# imu_3_xy.net
KiCad netlist of a schematic drawn in EAGLE
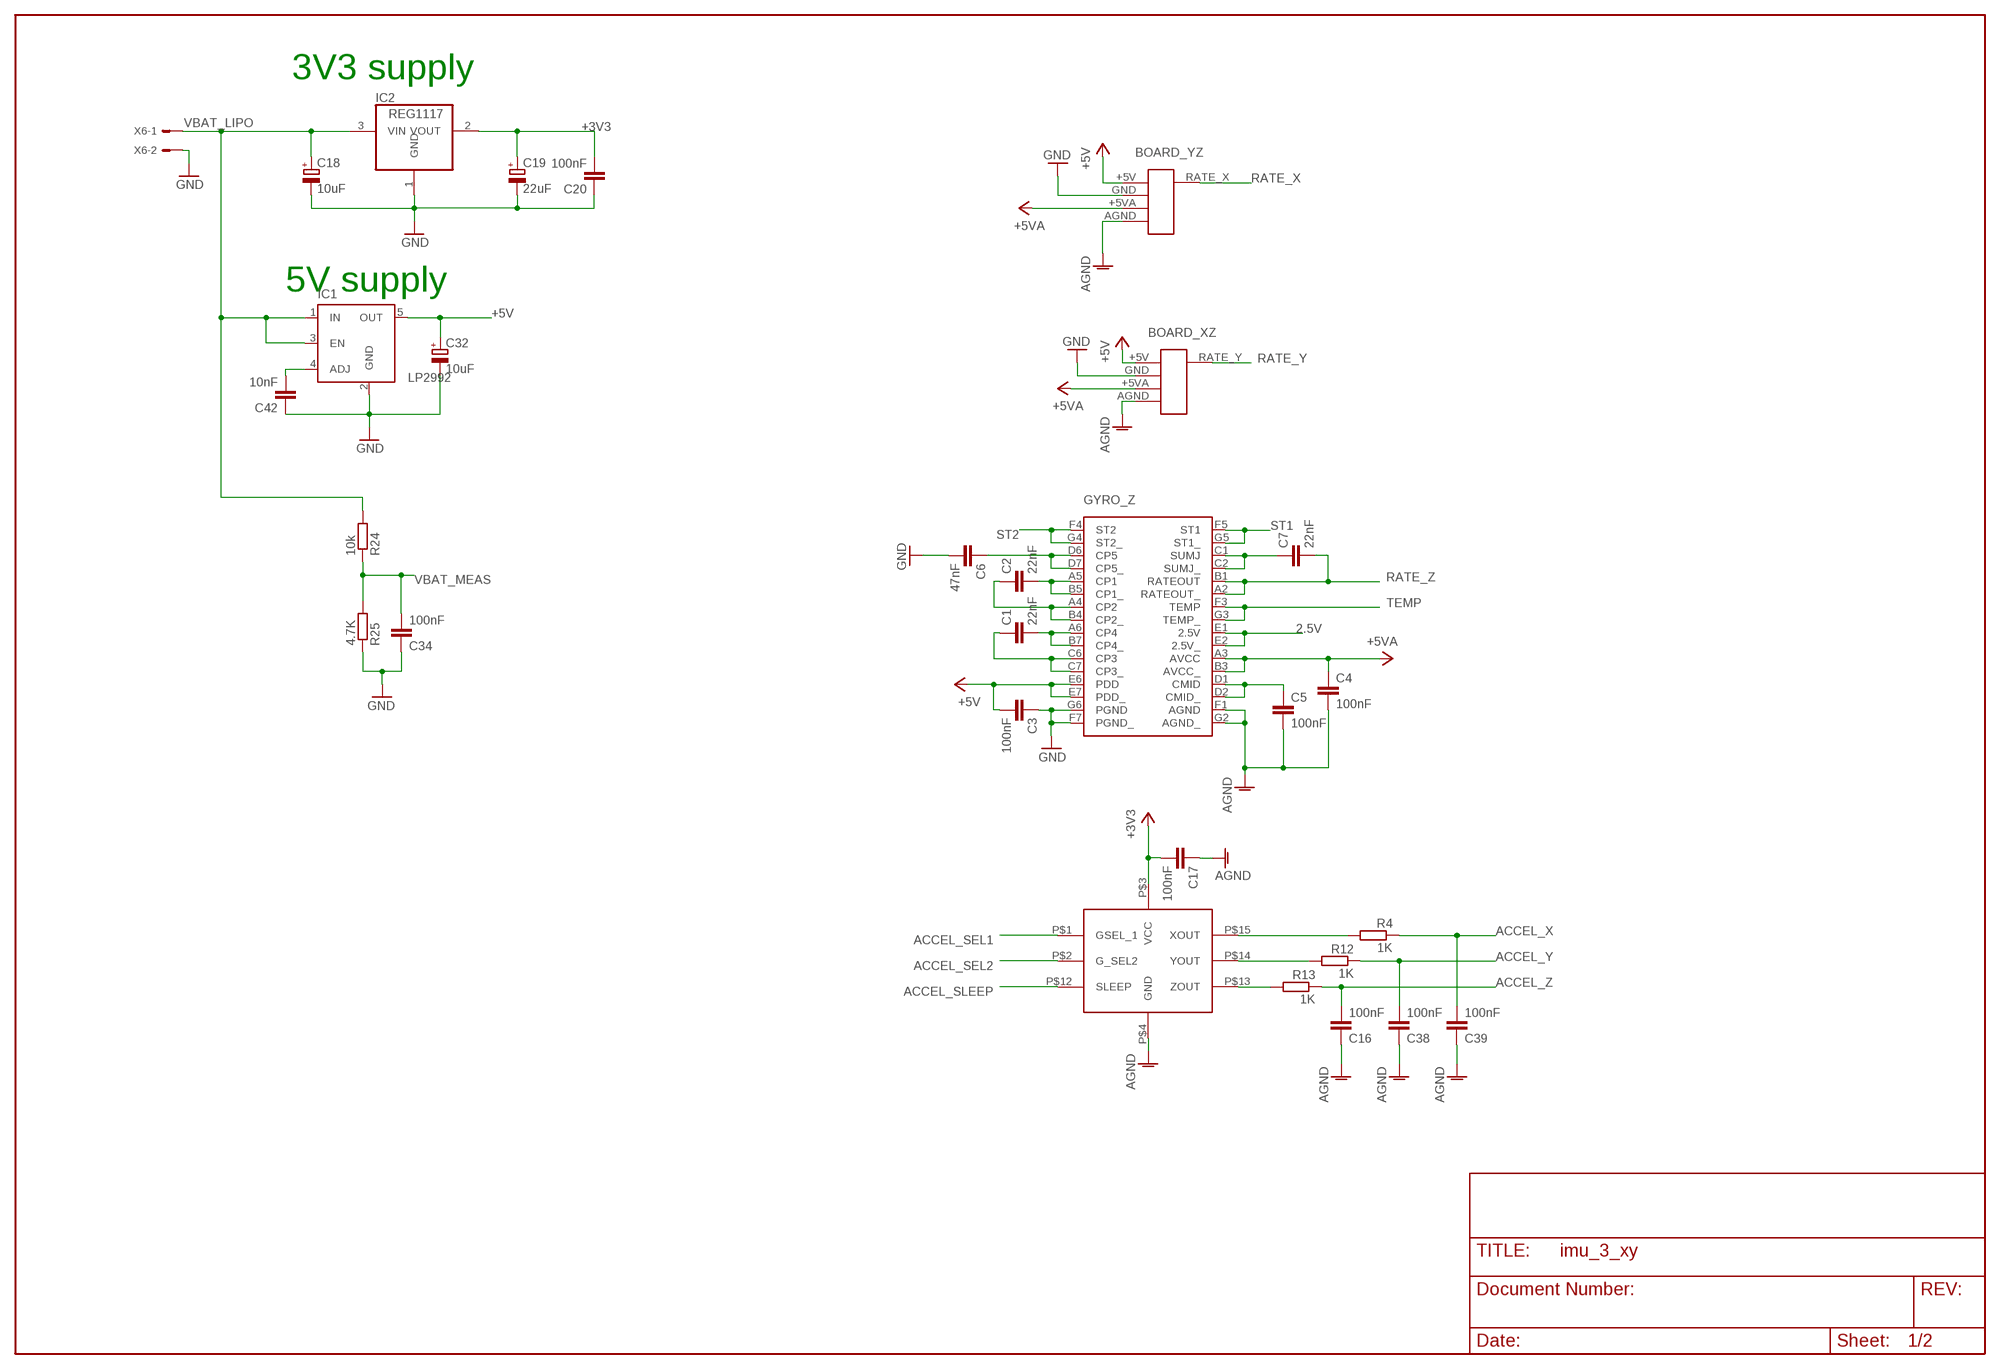
[diagram p0: schematic, sheet 1]
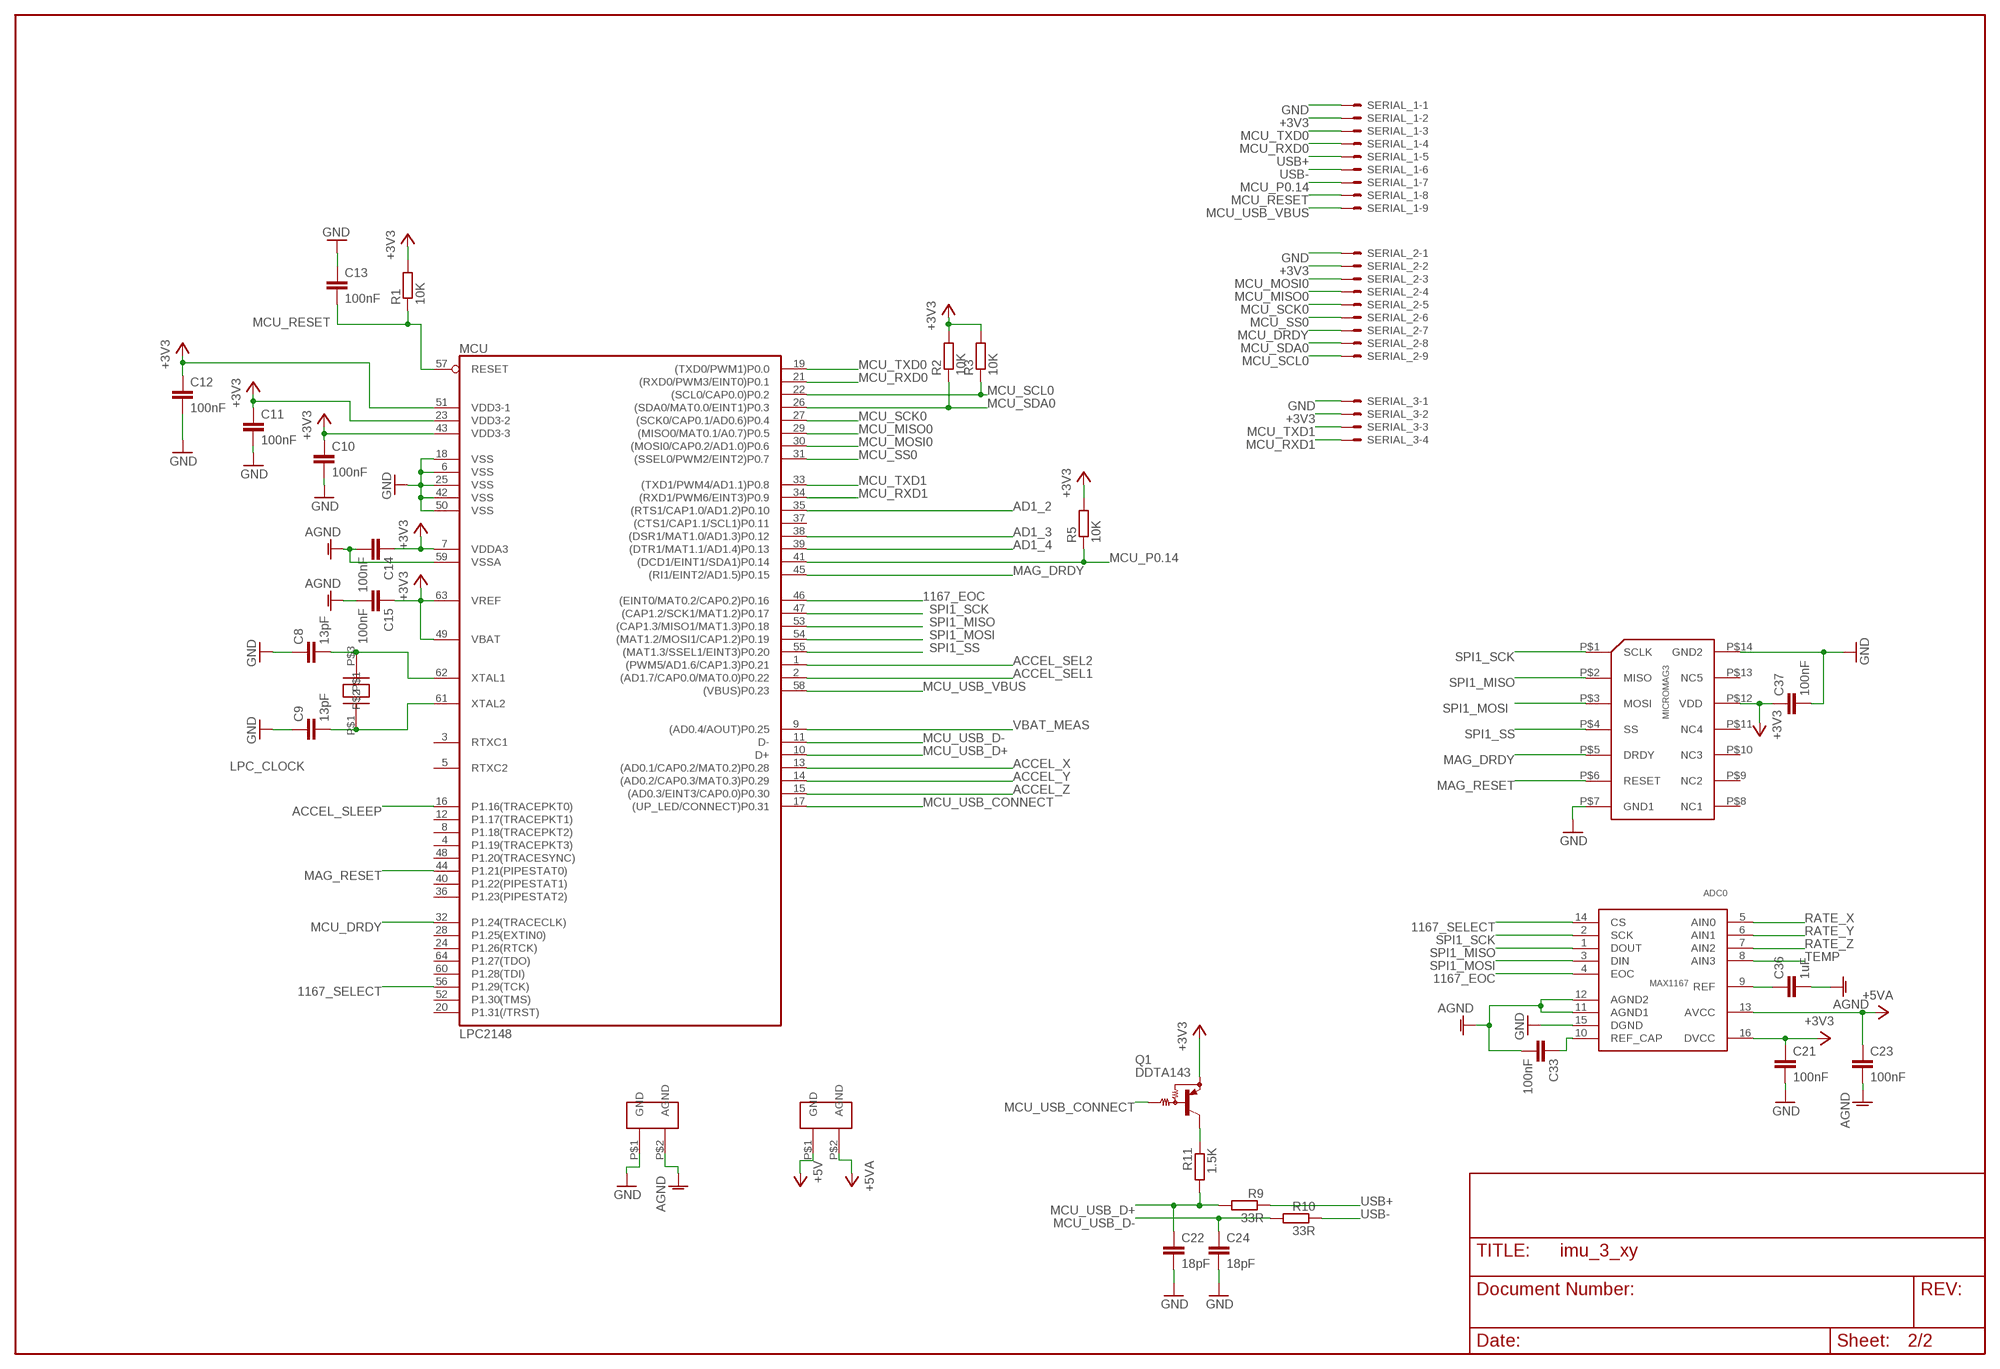
[diagram p1: schematic, sheet 2]

(export (version "E")
  (design (tool "Eeschema 10.0.6"))
  (components
    (comp (ref "ADC0")
      (value "MAX1167")
      (footprint "eagle-import:QSOP16")
      (libsource (lib "eagle-import") (part "MAX1167"))
    )
    (comp (ref "C8")
      (value "13pF")
      (footprint "eagle-import:C0402K")
      (libsource (lib "eagle-import") (part "C-EUC0402K"))
    )
    (comp (ref "C9")
      (value "13pF")
      (footprint "eagle-import:C0402K")
      (libsource (lib "eagle-import") (part "C-EUC0402K"))
    )
    (comp (ref "C10")
      (value "100nF")
      (footprint "eagle-import:C0402K")
      (libsource (lib "eagle-import") (part "C-EUC0402K"))
    )
    (comp (ref "C11")
      (value "100nF")
      (footprint "eagle-import:C0402K")
      (libsource (lib "eagle-import") (part "C-EUC0402K"))
    )
    (comp (ref "C12")
      (value "100nF")
      (footprint "eagle-import:C0402K")
      (libsource (lib "eagle-import") (part "C-EUC0402K"))
    )
    (comp (ref "C13")
      (value "100nF")
      (footprint "eagle-import:C0402K")
      (libsource (lib "eagle-import") (part "C-EUC0402K"))
    )
    (comp (ref "C14")
      (value "100nF")
      (footprint "eagle-import:C0402K")
      (libsource (lib "eagle-import") (part "C-EUC0402K"))
    )
    (comp (ref "C15")
      (value "100nF")
      (footprint "eagle-import:C0402K")
      (libsource (lib "eagle-import") (part "C-EUC0402K"))
    )
    (comp (ref "C21")
      (value "100nF")
      (footprint "eagle-import:C0402K")
      (libsource (lib "eagle-import") (part "C-EUC0402K"))
    )
    (comp (ref "C22")
      (value "18pF")
      (footprint "eagle-import:C0402K")
      (libsource (lib "eagle-import") (part "C-EUC0402K"))
    )
    (comp (ref "C23")
      (value "100nF")
      (footprint "eagle-import:C0402K")
      (libsource (lib "eagle-import") (part "C-EUC0402K"))
    )
    (comp (ref "C24")
      (value "18pF")
      (footprint "eagle-import:C0402K")
      (libsource (lib "eagle-import") (part "C-EUC0402K"))
    )
    (comp (ref "C33")
      (value "100nF")
      (footprint "eagle-import:C0402K")
      (libsource (lib "eagle-import") (part "C-EUC0402K"))
    )
    (comp (ref "C36")
      (value "1uF")
      (footprint "eagle-import:C0805")
      (libsource (lib "eagle-import") (part "C-EUC0805"))
    )
    (comp (ref "C37")
      (value "100nF")
      (footprint "eagle-import:C0402K")
      (libsource (lib "eagle-import") (part "C-EUC0402K"))
    )
    (comp (ref "CRYSTAL1")
      (value "14.764Mhz")
      (footprint "eagle-import:CTS_CRYSTAL")
      (libsource (lib "eagle-import") (part "CRYSTAL_CTS"))
    )
    (comp (ref "MCU")
      (value "LPC2148")
      (footprint "eagle-import:SQFP-S-10X10-64")
      (libsource (lib "eagle-import") (part "LPC2148"))
    )
    (comp (ref "Q1")
      (value "DDTA143")
      (footprint "eagle-import:SC59-BEC")
      (libsource (lib "eagle-import") (part "MUN2111T1"))
    )
    (comp (ref "R1")
      (value "10K")
      (footprint "eagle-import:R0402")
      (libsource (lib "eagle-import") (part "R-EU_R0402"))
    )
    (comp (ref "R2")
      (value "10K")
      (footprint "eagle-import:R0402")
      (libsource (lib "eagle-import") (part "R-EU_R0402"))
    )
    (comp (ref "R3")
      (value "10K")
      (footprint "eagle-import:R0402")
      (libsource (lib "eagle-import") (part "R-EU_R0402"))
    )
    (comp (ref "R5")
      (value "10K")
      (footprint "eagle-import:R0402")
      (libsource (lib "eagle-import") (part "R-EU_R0402"))
    )
    (comp (ref "R9")
      (value "33R")
      (footprint "eagle-import:R1005")
      (libsource (lib "eagle-import") (part "R-EU_R1005"))
    )
    (comp (ref "R10")
      (value "33R")
      (footprint "eagle-import:R1005")
      (libsource (lib "eagle-import") (part "R-EU_R1005"))
    )
    (comp (ref "R11")
      (value "1.5K")
      (footprint "eagle-import:R1005")
      (libsource (lib "eagle-import") (part "R-EU_R1005"))
    )
    (comp (ref "SERIAL_1")
      (value "53048-09")
      (footprint "eagle-import:53048-09")
      (libsource (lib "eagle-import") (part "53?-09048"))
    )
    (comp (ref "SERIAL_2")
      (value "53048-09")
      (footprint "eagle-import:53048-09")
      (libsource (lib "eagle-import") (part "53?-09048"))
    )
    (comp (ref "SERIAL_3")
      (value "53048-04")
      (footprint "eagle-import:53048-04")
      (libsource (lib "eagle-import") (part "53?-04048"))
    )
    (comp (ref "U$9")
      (value "MICROMAG3")
      (footprint "eagle-import:MICROMAG3")
      (libsource (lib "eagle-import") (part "MICROMAG3"))
    )
    (comp (ref "U$11")
      (value "TEST_CON_GP")
      (footprint "eagle-import:TEST_CON_GP")
      (libsource (lib "eagle-import") (part "TEST_CON_GP"))
    )
    (comp (ref "U$21")
      (value "TEST_CON_GP")
      (footprint "eagle-import:TEST_CON_GP")
      (libsource (lib "eagle-import") (part "TEST_CON_GP"))
    )
    (comp (ref "BOARD_XZ")
      (value "IMU_XZ_3")
      (footprint "eagle-import:IMU_XZ_3")
      (libsource (lib "eagle-import") (part "IMU_XZ_3"))
    )
    (comp (ref "BOARD_YZ")
      (value "IMU_YZ_3")
      (footprint "eagle-import:IMU_YZ_3")
      (libsource (lib "eagle-import") (part "IMU_YZ_3"))
    )
    (comp (ref "C1")
      (value "22nF")
      (footprint "eagle-import:C0402K")
      (libsource (lib "eagle-import") (part "C-EUC0402K"))
    )
    (comp (ref "C2")
      (value "22nF")
      (footprint "eagle-import:C0402K")
      (libsource (lib "eagle-import") (part "C-EUC0402K"))
    )
    (comp (ref "C3")
      (value "100nF")
      (footprint "eagle-import:C0402K")
      (libsource (lib "eagle-import") (part "C-EUC0402K"))
    )
    (comp (ref "C4")
      (value "100nF")
      (footprint "eagle-import:C0402K")
      (libsource (lib "eagle-import") (part "C-EUC0402K"))
    )
    (comp (ref "C5")
      (value "100nF")
      (footprint "eagle-import:C0402K")
      (libsource (lib "eagle-import") (part "C-EUC0402K"))
    )
    (comp (ref "C6")
      (value "47nF")
      (footprint "eagle-import:C0402K")
      (libsource (lib "eagle-import") (part "C-EUC0402K"))
    )
    (comp (ref "C7")
      (value "22nF")
      (footprint "eagle-import:C0402K")
      (libsource (lib "eagle-import") (part "C-EUC0402K"))
    )
    (comp (ref "C16")
      (value "100nF")
      (footprint "eagle-import:C0402K")
      (libsource (lib "eagle-import") (part "C-EUC0402K"))
    )
    (comp (ref "C17")
      (value "100nF")
      (footprint "eagle-import:C0402K")
      (libsource (lib "eagle-import") (part "C-EUC0402K"))
    )
    (comp (ref "C18")
      (value "10uF")
      (footprint "eagle-import:A_3216-18R")
      (libsource (lib "eagle-import") (part "CPOL-EUA/3216-18R"))
    )
    (comp (ref "C19")
      (value "22uF")
      (footprint "eagle-import:B_3528-21R")
      (libsource (lib "eagle-import") (part "CPOL-EUB/3528-21R"))
    )
    (comp (ref "C20")
      (value "100nF")
      (footprint "eagle-import:C0603K")
      (libsource (lib "eagle-import") (part "C-EUC0603K"))
    )
    (comp (ref "C32")
      (value "10uF")
      (footprint "eagle-import:A_3216-18R")
      (libsource (lib "eagle-import") (part "CPOL-EUA/3216-18R"))
    )
    (comp (ref "C34")
      (value "100nF")
      (footprint "eagle-import:C0402K")
      (libsource (lib "eagle-import") (part "C-EUC0402K"))
    )
    (comp (ref "C38")
      (value "100nF")
      (footprint "eagle-import:C0402K")
      (libsource (lib "eagle-import") (part "C-EUC0402K"))
    )
    (comp (ref "C39")
      (value "100nF")
      (footprint "eagle-import:C0402K")
      (libsource (lib "eagle-import") (part "C-EUC0402K"))
    )
    (comp (ref "C42")
      (value "10nF")
      (footprint "eagle-import:C0402K")
      (libsource (lib "eagle-import") (part "C-EUC0402K"))
    )
    (comp (ref "GYRO_Z")
      (value "ADXR")
      (footprint "eagle-import:BC-32")
      (libsource (lib "eagle-import") (part "ADXR"))
    )
    (comp (ref "IC1")
      (value "LP2992")
      (footprint "eagle-import:SOT23-5")
      (libsource (lib "eagle-import") (part "MIC5219BM5"))
    )
    (comp (ref "IC2")
      (value "REG1117")
      (footprint "eagle-import:SOT223")
      (libsource (lib "eagle-import") (part "REG1117"))
    )
    (comp (ref "R4")
      (value "1K")
      (footprint "eagle-import:R0402")
      (libsource (lib "eagle-import") (part "R-EU_R0402"))
    )
    (comp (ref "R12")
      (value "1K")
      (footprint "eagle-import:R0402")
      (libsource (lib "eagle-import") (part "R-EU_R0402"))
    )
    (comp (ref "R13")
      (value "1K")
      (footprint "eagle-import:R0402")
      (libsource (lib "eagle-import") (part "R-EU_R0402"))
    )
    (comp (ref "R24")
      (value "10k")
      (footprint "eagle-import:R0402")
      (libsource (lib "eagle-import") (part "R-EU_R0402"))
    )
    (comp (ref "R25")
      (value "4.7K")
      (footprint "eagle-import:R0402")
      (libsource (lib "eagle-import") (part "R-EU_R0402"))
    )
    (comp (ref "U$5")
      (value "MMA7260")
      (footprint "eagle-import:CASE162201")
      (libsource (lib "eagle-import") (part "MMA7260"))
    )
    (comp (ref "X6")
      (value "53048-02")
      (footprint "eagle-import:53048-02")
      (libsource (lib "eagle-import") (part "53?-02048"))
    )
  )
  (nets
    (net (code "1") (name "+3V3") (class "Default")
      (node (ref "ADC0") (pin "16") (pinfunction "DVCC_16") (pintype "bidirectional"))
      (node (ref "C10") (pin "1") (pinfunction "1_1") (pintype "passive"))
      (node (ref "C11") (pin "1") (pinfunction "1_1") (pintype "passive"))
      (node (ref "C12") (pin "1") (pinfunction "1_1") (pintype "passive"))
      (node (ref "C14") (pin "1") (pinfunction "1_1") (pintype "passive"))
      (node (ref "C15") (pin "1") (pinfunction "1_1") (pintype "passive"))
      (node (ref "C17") (pin "2") (pinfunction "2_2") (pintype "passive"))
      (node (ref "C19") (pin "+") (pinfunction "+_+") (pintype "passive"))
      (node (ref "C20") (pin "2") (pinfunction "2_2") (pintype "passive"))
      (node (ref "C21") (pin "1") (pinfunction "1_1") (pintype "passive"))
      (node (ref "C37") (pin "1") (pinfunction "1_1") (pintype "passive"))
      (node (ref "IC2") (pin "2") (pinfunction "VOUT_2") (pintype "output"))
      (node (ref "MCU") (pin "23") (pinfunction "VDD3-2_23") (pintype "power_in"))
      (node (ref "MCU") (pin "43") (pinfunction "VDD3-3_43") (pintype "power_in"))
      (node (ref "MCU") (pin "49") (pinfunction "VBAT_49") (pintype "power_in"))
      (node (ref "MCU") (pin "51") (pinfunction "VDD3-1_51") (pintype "power_in"))
      (node (ref "MCU") (pin "63") (pinfunction "VREF_63") (pintype "input"))
      (node (ref "MCU") (pin "7") (pinfunction "VDDA3_7") (pintype "power_in"))
      (node (ref "Q1") (pin "E") (pinfunction "E_E") (pintype "passive"))
      (node (ref "R1") (pin "2") (pinfunction "2_2") (pintype "passive"))
      (node (ref "R2") (pin "2") (pinfunction "2_2") (pintype "passive"))
      (node (ref "R3") (pin "2") (pinfunction "2_2") (pintype "passive"))
      (node (ref "R5") (pin "2") (pinfunction "2_2") (pintype "passive"))
      (node (ref "SERIAL_1") (pin "2") (pinfunction "S_2") (pintype "passive"))
      (node (ref "SERIAL_2") (pin "2") (pinfunction "S_2") (pintype "passive"))
      (node (ref "SERIAL_3") (pin "2") (pinfunction "S_2") (pintype "passive"))
      (node (ref "U$5") (pin "P$3") (pinfunction "VCC_P$3") (pintype "bidirectional"))
      (node (ref "U$9") (pin "P$12") (pinfunction "VDD_P$12") (pintype "bidirectional"))
    )
    (net (code "2") (name "+5V") (class "Default")
      (node (ref "BOARD_XZ") (pin "+5V") (pinfunction "+5V_+5V") (pintype "bidirectional"))
      (node (ref "BOARD_YZ") (pin "+5V") (pinfunction "+5V_+5V") (pintype "bidirectional"))
      (node (ref "C3") (pin "2") (pinfunction "2_2") (pintype "passive"))
      (node (ref "C32") (pin "+") (pinfunction "+_+") (pintype "passive"))
      (node (ref "GYRO_Z") (pin "E6") (pinfunction "PDD_E6") (pintype "bidirectional"))
      (node (ref "GYRO_Z") (pin "E7") (pinfunction "PDD__E7") (pintype "bidirectional"))
      (node (ref "IC1") (pin "5") (pinfunction "OUT_5") (pintype "output"))
      (node (ref "U$21") (pin "P$1") (pinfunction "GND_P$1") (pintype "bidirectional"))
    )
    (net (code "3") (name "+5VA") (class "Default")
      (node (ref "ADC0") (pin "13") (pinfunction "AVCC_13") (pintype "bidirectional"))
      (node (ref "BOARD_XZ") (pin "+5VA") (pinfunction "+5VA_+5VA") (pintype "bidirectional"))
      (node (ref "BOARD_YZ") (pin "+5VA") (pinfunction "+5VA_+5VA") (pintype "bidirectional"))
      (node (ref "C23") (pin "1") (pinfunction "1_1") (pintype "passive"))
      (node (ref "C4") (pin "1") (pinfunction "1_1") (pintype "passive"))
      (node (ref "GYRO_Z") (pin "A3") (pinfunction "AVCC_A3") (pintype "bidirectional"))
      (node (ref "GYRO_Z") (pin "B3") (pinfunction "AVCC__B3") (pintype "bidirectional"))
      (node (ref "U$21") (pin "P$2") (pinfunction "AGND_P$2") (pintype "bidirectional"))
    )
    (net (code "4") (name "2.5V") (class "Default")
      (node (ref "GYRO_Z") (pin "E1") (pinfunction "2.5V_E1") (pintype "bidirectional"))
      (node (ref "GYRO_Z") (pin "E2") (pinfunction "2.5V__E2") (pintype "bidirectional"))
    )
    (net (code "5") (name "1167_EOC") (class "Default")
      (node (ref "ADC0") (pin "4") (pinfunction "EOC_4") (pintype "bidirectional"))
      (node (ref "MCU") (pin "46") (pinfunction "(EINT0/MAT0.2/CAP0.2)P0.16_46") (pintype "bidirectional"))
    )
    (net (code "6") (name "1167_SELECT") (class "Default")
      (node (ref "ADC0") (pin "14") (pinfunction "CS_14") (pintype "bidirectional"))
      (node (ref "MCU") (pin "56") (pinfunction "P1.29(TCK)_56") (pintype "bidirectional"))
    )
    (net (code "7") (name "ACCEL_SEL1") (class "Default")
      (node (ref "MCU") (pin "2") (pinfunction "(AD1.7/CAP0.0/MAT0.0)P0.22_2") (pintype "bidirectional"))
      (node (ref "U$5") (pin "P$1") (pinfunction "GSEL_1_P$1") (pintype "bidirectional"))
    )
    (net (code "8") (name "ACCEL_SEL2") (class "Default")
      (node (ref "MCU") (pin "1") (pinfunction "(PWM5/AD1.6/CAP1.3)P0.21_1") (pintype "bidirectional"))
      (node (ref "U$5") (pin "P$2") (pinfunction "G_SEL2_P$2") (pintype "bidirectional"))
    )
    (net (code "9") (name "ACCEL_SLEEP") (class "Default")
      (node (ref "MCU") (pin "16") (pinfunction "P1.16(TRACEPKT0)_16") (pintype "bidirectional"))
      (node (ref "U$5") (pin "P$12") (pinfunction "SLEEP_P$12") (pintype "bidirectional"))
    )
    (net (code "10") (name "ACCEL_X") (class "Default")
      (node (ref "C39") (pin "2") (pinfunction "2_2") (pintype "passive"))
      (node (ref "MCU") (pin "13") (pinfunction "(AD0.1/CAP0.2/MAT0.2)P0.28_13") (pintype "bidirectional"))
      (node (ref "R4") (pin "1") (pinfunction "1_1") (pintype "passive"))
    )
    (net (code "11") (name "ACCEL_Y") (class "Default")
      (node (ref "C38") (pin "2") (pinfunction "2_2") (pintype "passive"))
      (node (ref "MCU") (pin "14") (pinfunction "(AD0.2/CAP0.3/MAT0.3)P0.29_14") (pintype "bidirectional"))
      (node (ref "R12") (pin "1") (pinfunction "1_1") (pintype "passive"))
    )
    (net (code "12") (name "ACCEL_Z") (class "Default")
      (node (ref "C16") (pin "2") (pinfunction "2_2") (pintype "passive"))
      (node (ref "MCU") (pin "15") (pinfunction "(AD0.3/EINT3/CAP0.0)P0.30_15") (pintype "bidirectional"))
      (node (ref "R13") (pin "1") (pinfunction "1_1") (pintype "passive"))
    )
    (net (code "13") (name "AD1_2") (class "Default")
      (node (ref "MCU") (pin "35") (pinfunction "(RTS1/CAP1.0/AD1.2)P0.10_35") (pintype "bidirectional"))
    )
    (net (code "14") (name "AD1_3") (class "Default")
      (node (ref "MCU") (pin "38") (pinfunction "(DSR1/MAT1.0/AD1.3)P0.12_38") (pintype "bidirectional"))
    )
    (net (code "15") (name "AD1_4") (class "Default")
      (node (ref "MCU") (pin "39") (pinfunction "(DTR1/MAT1.1/AD1.4)P0.13_39") (pintype "bidirectional"))
    )
    (net (code "16") (name "AGND") (class "Default")
      (node (ref "ADC0") (pin "11") (pinfunction "AGND1_11") (pintype "bidirectional"))
      (node (ref "ADC0") (pin "12") (pinfunction "AGND2_12") (pintype "bidirectional"))
      (node (ref "BOARD_XZ") (pin "AGND") (pinfunction "AGND_AGND") (pintype "bidirectional"))
      (node (ref "BOARD_YZ") (pin "AGND") (pinfunction "AGND_AGND") (pintype "bidirectional"))
      (node (ref "C14") (pin "2") (pinfunction "2_2") (pintype "passive"))
      (node (ref "C15") (pin "2") (pinfunction "2_2") (pintype "passive"))
      (node (ref "C16") (pin "1") (pinfunction "1_1") (pintype "passive"))
      (node (ref "C17") (pin "1") (pinfunction "1_1") (pintype "passive"))
      (node (ref "C23") (pin "2") (pinfunction "2_2") (pintype "passive"))
      (node (ref "C33") (pin "2") (pinfunction "2_2") (pintype "passive"))
      (node (ref "C36") (pin "2") (pinfunction "2_2") (pintype "passive"))
      (node (ref "C38") (pin "1") (pinfunction "1_1") (pintype "passive"))
      (node (ref "C39") (pin "1") (pinfunction "1_1") (pintype "passive"))
      (node (ref "C4") (pin "2") (pinfunction "2_2") (pintype "passive"))
      (node (ref "C5") (pin "2") (pinfunction "2_2") (pintype "passive"))
      (node (ref "GYRO_Z") (pin "F1") (pinfunction "AGND_F1") (pintype "bidirectional"))
      (node (ref "GYRO_Z") (pin "G2") (pinfunction "AGND__G2") (pintype "bidirectional"))
      (node (ref "MCU") (pin "59") (pinfunction "VSSA_59") (pintype "power_in"))
      (node (ref "U$11") (pin "P$2") (pinfunction "AGND_P$2") (pintype "bidirectional"))
      (node (ref "U$5") (pin "P$4") (pinfunction "GND_P$4") (pintype "bidirectional"))
    )
    (net (code "17") (name "GND") (class "Default")
      (node (ref "ADC0") (pin "15") (pinfunction "DGND_15") (pintype "bidirectional"))
      (node (ref "BOARD_XZ") (pin "GND") (pinfunction "GND_GND") (pintype "bidirectional"))
      (node (ref "BOARD_YZ") (pin "GND") (pinfunction "GND_GND") (pintype "bidirectional"))
      (node (ref "C10") (pin "2") (pinfunction "2_2") (pintype "passive"))
      (node (ref "C11") (pin "2") (pinfunction "2_2") (pintype "passive"))
      (node (ref "C12") (pin "2") (pinfunction "2_2") (pintype "passive"))
      (node (ref "C13") (pin "1") (pinfunction "1_1") (pintype "passive"))
      (node (ref "C18") (pin "-") (pinfunction "-_-") (pintype "passive"))
      (node (ref "C19") (pin "-") (pinfunction "-_-") (pintype "passive"))
      (node (ref "C20") (pin "1") (pinfunction "1_1") (pintype "passive"))
      (node (ref "C21") (pin "2") (pinfunction "2_2") (pintype "passive"))
      (node (ref "C22") (pin "2") (pinfunction "2_2") (pintype "passive"))
      (node (ref "C24") (pin "2") (pinfunction "2_2") (pintype "passive"))
      (node (ref "C3") (pin "1") (pinfunction "1_1") (pintype "passive"))
      (node (ref "C32") (pin "-") (pinfunction "-_-") (pintype "passive"))
      (node (ref "C34") (pin "1") (pinfunction "1_1") (pintype "passive"))
      (node (ref "C37") (pin "2") (pinfunction "2_2") (pintype "passive"))
      (node (ref "C42") (pin "1") (pinfunction "1_1") (pintype "passive"))
      (node (ref "C6") (pin "2") (pinfunction "2_2") (pintype "passive"))
      (node (ref "C8") (pin "1") (pinfunction "1_1") (pintype "passive"))
      (node (ref "C9") (pin "1") (pinfunction "1_1") (pintype "passive"))
      (node (ref "GYRO_Z") (pin "F7") (pinfunction "PGND__F7") (pintype "bidirectional"))
      (node (ref "GYRO_Z") (pin "G6") (pinfunction "PGND_G6") (pintype "bidirectional"))
      (node (ref "IC1") (pin "2") (pinfunction "GND_2") (pintype "power_in"))
      (node (ref "IC2") (pin "1") (pinfunction "GND_1") (pintype "power_in"))
      (node (ref "MCU") (pin "18") (pinfunction "VSS_18") (pintype "power_in"))
      (node (ref "MCU") (pin "25") (pinfunction "VSS_25") (pintype "power_in"))
      (node (ref "MCU") (pin "42") (pinfunction "VSS_42") (pintype "power_in"))
      (node (ref "MCU") (pin "50") (pinfunction "VSS_50") (pintype "power_in"))
      (node (ref "MCU") (pin "6") (pinfunction "VSS_6") (pintype "power_in"))
      (node (ref "R25") (pin "1") (pinfunction "1_1") (pintype "passive"))
      (node (ref "SERIAL_1") (pin "1") (pinfunction "S_1") (pintype "passive"))
      (node (ref "SERIAL_2") (pin "1") (pinfunction "S_1") (pintype "passive"))
      (node (ref "SERIAL_3") (pin "1") (pinfunction "S_1") (pintype "passive"))
      (node (ref "U$11") (pin "P$1") (pinfunction "GND_P$1") (pintype "bidirectional"))
      (node (ref "U$9") (pin "P$14") (pinfunction "GND2_P$14") (pintype "bidirectional"))
      (node (ref "U$9") (pin "P$7") (pinfunction "GND1_P$7") (pintype "bidirectional"))
      (node (ref "X6") (pin "2") (pinfunction "S_2") (pintype "passive"))
    )
    (net (code "18") (name "LPC_CLOCK") (class "Default")
      (node (ref "C9") (pin "2") (pinfunction "2_2") (pintype "passive"))
      (node (ref "CRYSTAL1") (pin "P$1") (pinfunction "P$1_P$1") (pintype "bidirectional"))
      (node (ref "MCU") (pin "61") (pinfunction "XTAL2_61") (pintype "output"))
    )
    (net (code "19") (name "MAG_DRDY") (class "Default")
      (node (ref "MCU") (pin "45") (pinfunction "(RI1/EINT2/AD1.5)P0.15_45") (pintype "bidirectional"))
      (node (ref "U$9") (pin "P$5") (pinfunction "DRDY_P$5") (pintype "bidirectional"))
    )
    (net (code "20") (name "MAG_RESET") (class "Default")
      (node (ref "MCU") (pin "44") (pinfunction "P1.21(PIPESTAT0)_44") (pintype "bidirectional"))
      (node (ref "U$9") (pin "P$6") (pinfunction "RESET_P$6") (pintype "bidirectional"))
    )
    (net (code "21") (name "MCU_DRDY") (class "Default")
      (node (ref "MCU") (pin "32") (pinfunction "P1.24(TRACECLK)_32") (pintype "bidirectional"))
      (node (ref "SERIAL_2") (pin "7") (pinfunction "S_7") (pintype "passive"))
    )
    (net (code "22") (name "MCU_MISO0") (class "Default")
      (node (ref "MCU") (pin "29") (pinfunction "(MISO0/MAT0.1/A0.7)P0.5_29") (pintype "bidirectional"))
      (node (ref "SERIAL_2") (pin "4") (pinfunction "S_4") (pintype "passive"))
    )
    (net (code "23") (name "MCU_MOSI0") (class "Default")
      (node (ref "MCU") (pin "30") (pinfunction "(MOSI0/CAP0.2/AD1.0)P0.6_30") (pintype "bidirectional"))
      (node (ref "SERIAL_2") (pin "3") (pinfunction "S_3") (pintype "passive"))
    )
    (net (code "24") (name "MCU_P0.14") (class "Default")
      (node (ref "MCU") (pin "41") (pinfunction "(DCD1/EINT1/SDA1)P0.14_41") (pintype "bidirectional"))
      (node (ref "R5") (pin "1") (pinfunction "1_1") (pintype "passive"))
      (node (ref "SERIAL_1") (pin "7") (pinfunction "S_7") (pintype "passive"))
    )
    (net (code "25") (name "MCU_RESET") (class "Default")
      (node (ref "C13") (pin "2") (pinfunction "2_2") (pintype "passive"))
      (node (ref "MCU") (pin "57") (pinfunction "RESET_57") (pintype "input"))
      (node (ref "R1") (pin "1") (pinfunction "1_1") (pintype "passive"))
      (node (ref "SERIAL_1") (pin "8") (pinfunction "S_8") (pintype "passive"))
    )
    (net (code "26") (name "MCU_RXD0") (class "Default")
      (node (ref "MCU") (pin "21") (pinfunction "(RXD0/PWM3/EINT0)P0.1_21") (pintype "bidirectional"))
      (node (ref "SERIAL_1") (pin "4") (pinfunction "S_4") (pintype "passive"))
    )
    (net (code "27") (name "MCU_RXD1") (class "Default")
      (node (ref "MCU") (pin "34") (pinfunction "(RXD1/PWM6/EINT3)P0.9_34") (pintype "bidirectional"))
      (node (ref "SERIAL_3") (pin "4") (pinfunction "S_4") (pintype "passive"))
    )
    (net (code "28") (name "MCU_SCK0") (class "Default")
      (node (ref "MCU") (pin "27") (pinfunction "(SCK0/CAP0.1/AD0.6)P0.4_27") (pintype "bidirectional"))
      (node (ref "SERIAL_2") (pin "5") (pinfunction "S_5") (pintype "passive"))
    )
    (net (code "29") (name "MCU_SCL0") (class "Default")
      (node (ref "MCU") (pin "22") (pinfunction "(SCL0/CAP0.0)P0.2_22") (pintype "bidirectional"))
      (node (ref "R3") (pin "1") (pinfunction "1_1") (pintype "passive"))
      (node (ref "SERIAL_2") (pin "9") (pinfunction "S_9") (pintype "passive"))
    )
    (net (code "30") (name "MCU_SDA0") (class "Default")
      (node (ref "MCU") (pin "26") (pinfunction "(SDA0/MAT0.0/EINT1)P0.3_26") (pintype "bidirectional"))
      (node (ref "R2") (pin "1") (pinfunction "1_1") (pintype "passive"))
      (node (ref "SERIAL_2") (pin "8") (pinfunction "S_8") (pintype "passive"))
    )
    (net (code "31") (name "MCU_SS0") (class "Default")
      (node (ref "MCU") (pin "31") (pinfunction "(SSEL0/PWM2/EINT2)P0.7_31") (pintype "bidirectional"))
      (node (ref "SERIAL_2") (pin "6") (pinfunction "S_6") (pintype "passive"))
    )
    (net (code "32") (name "MCU_TXD0") (class "Default")
      (node (ref "MCU") (pin "19") (pinfunction "(TXD0/PWM1)P0.0_19") (pintype "bidirectional"))
      (node (ref "SERIAL_1") (pin "3") (pinfunction "S_3") (pintype "passive"))
    )
    (net (code "33") (name "MCU_TXD1") (class "Default")
      (node (ref "MCU") (pin "33") (pinfunction "(TXD1/PWM4/AD1.1)P0.8_33") (pintype "bidirectional"))
      (node (ref "SERIAL_3") (pin "3") (pinfunction "S_3") (pintype "passive"))
    )
    (net (code "34") (name "MCU_USB_CONNECT") (class "Default")
      (node (ref "MCU") (pin "17") (pinfunction "(UP_LED/CONNECT)P0.31_17") (pintype "output"))
      (node (ref "Q1") (pin "B") (pinfunction "B_B") (pintype "passive"))
    )
    (net (code "35") (name "MCU_USB_D+") (class "Default")
      (node (ref "C22") (pin "1") (pinfunction "1_1") (pintype "passive"))
      (node (ref "MCU") (pin "10") (pinfunction "D+_10") (pintype "bidirectional"))
      (node (ref "R11") (pin "2") (pinfunction "2_2") (pintype "passive"))
      (node (ref "R9") (pin "2") (pinfunction "2_2") (pintype "passive"))
    )
    (net (code "36") (name "MCU_USB_D-") (class "Default")
      (node (ref "C24") (pin "1") (pinfunction "1_1") (pintype "passive"))
      (node (ref "MCU") (pin "11") (pinfunction "D-_11") (pintype "bidirectional"))
      (node (ref "R10") (pin "2") (pinfunction "2_2") (pintype "passive"))
    )
    (net (code "37") (name "MCU_USB_VBUS") (class "Default")
      (node (ref "MCU") (pin "58") (pinfunction "(VBUS)P0.23_58") (pintype "bidirectional"))
      (node (ref "SERIAL_1") (pin "9") (pinfunction "S_9") (pintype "passive"))
    )
    (net (code "38") (name "Net-(ADC0-REF)") (class "Default")
      (node (ref "ADC0") (pin "9") (pinfunction "REF_9") (pintype "bidirectional"))
      (node (ref "C36") (pin "1") (pinfunction "1_1") (pintype "passive"))
    )
    (net (code "39") (name "Net-(ADC0-REF_CAP)") (class "Default")
      (node (ref "ADC0") (pin "10") (pinfunction "REF_CAP_10") (pintype "bidirectional"))
      (node (ref "C33") (pin "1") (pinfunction "1_1") (pintype "passive"))
    )
    (net (code "40") (name "Net-(CRYSTAL1-P$2)") (class "Default")
      (node (ref "C8") (pin "2") (pinfunction "2_2") (pintype "passive"))
      (node (ref "CRYSTAL1") (pin "P$3") (pinfunction "P$2_P$3") (pintype "bidirectional"))
      (node (ref "MCU") (pin "62") (pinfunction "XTAL1_62") (pintype "input"))
    )
    (net (code "41") (name "Net-(GYRO_Z-CMID)") (class "Default")
      (node (ref "C5") (pin "1") (pinfunction "1_1") (pintype "passive"))
      (node (ref "GYRO_Z") (pin "D1") (pinfunction "CMID_D1") (pintype "bidirectional"))
      (node (ref "GYRO_Z") (pin "D2") (pinfunction "CMID__D2") (pintype "bidirectional"))
    )
    (net (code "42") (name "Net-(GYRO_Z-CP1)") (class "Default")
      (node (ref "C2") (pin "2") (pinfunction "2_2") (pintype "passive"))
      (node (ref "GYRO_Z") (pin "A5") (pinfunction "CP1_A5") (pintype "bidirectional"))
      (node (ref "GYRO_Z") (pin "B5") (pinfunction "CP1__B5") (pintype "bidirectional"))
    )
    (net (code "43") (name "Net-(GYRO_Z-CP2)") (class "Default")
      (node (ref "C2") (pin "1") (pinfunction "1_1") (pintype "passive"))
      (node (ref "GYRO_Z") (pin "A4") (pinfunction "CP2_A4") (pintype "bidirectional"))
      (node (ref "GYRO_Z") (pin "B4") (pinfunction "CP2__B4") (pintype "bidirectional"))
    )
    (net (code "44") (name "Net-(GYRO_Z-CP3)") (class "Default")
      (node (ref "C1") (pin "1") (pinfunction "1_1") (pintype "passive"))
      (node (ref "GYRO_Z") (pin "C6") (pinfunction "CP3_C6") (pintype "bidirectional"))
      (node (ref "GYRO_Z") (pin "C7") (pinfunction "CP3__C7") (pintype "bidirectional"))
    )
    (net (code "45") (name "Net-(GYRO_Z-CP4)") (class "Default")
      (node (ref "C1") (pin "2") (pinfunction "2_2") (pintype "passive"))
      (node (ref "GYRO_Z") (pin "A6") (pinfunction "CP4_A6") (pintype "bidirectional"))
      (node (ref "GYRO_Z") (pin "B7") (pinfunction "CP4__B7") (pintype "bidirectional"))
    )
    (net (code "46") (name "Net-(GYRO_Z-CP5)") (class "Default")
      (node (ref "C6") (pin "1") (pinfunction "1_1") (pintype "passive"))
      (node (ref "GYRO_Z") (pin "D6") (pinfunction "CP5_D6") (pintype "bidirectional"))
      (node (ref "GYRO_Z") (pin "D7") (pinfunction "CP5__D7") (pintype "bidirectional"))
    )
    (net (code "47") (name "Net-(GYRO_Z-SUMJ)") (class "Default")
      (node (ref "C7") (pin "1") (pinfunction "1_1") (pintype "passive"))
      (node (ref "GYRO_Z") (pin "C1") (pinfunction "SUMJ_C1") (pintype "bidirectional"))
      (node (ref "GYRO_Z") (pin "C2") (pinfunction "SUMJ__C2") (pintype "bidirectional"))
    )
    (net (code "48") (name "Net-(IC1-ADJ)") (class "Default")
      (node (ref "C42") (pin "2") (pinfunction "2_2") (pintype "passive"))
      (node (ref "IC1") (pin "4") (pinfunction "ADJ_4") (pintype "passive"))
    )
    (net (code "49") (name "Net-(Q1-PadC)") (class "Default")
      (node (ref "Q1") (pin "C") (pinfunction "C_C") (pintype "passive"))
      (node (ref "R11") (pin "1") (pinfunction "1_1") (pintype "passive"))
    )
    (net (code "50") (name "Net-(U$5-XOUT)") (class "Default")
      (node (ref "R4") (pin "2") (pinfunction "2_2") (pintype "passive"))
      (node (ref "U$5") (pin "P$15") (pinfunction "XOUT_P$15") (pintype "bidirectional"))
    )
    (net (code "51") (name "Net-(U$5-YOUT)") (class "Default")
      (node (ref "R12") (pin "2") (pinfunction "2_2") (pintype "passive"))
      (node (ref "U$5") (pin "P$14") (pinfunction "YOUT_P$14") (pintype "bidirectional"))
    )
    (net (code "52") (name "Net-(U$5-ZOUT)") (class "Default")
      (node (ref "R13") (pin "2") (pinfunction "2_2") (pintype "passive"))
      (node (ref "U$5") (pin "P$13") (pinfunction "ZOUT_P$13") (pintype "bidirectional"))
    )
    (net (code "53") (name "RATE_X") (class "Default")
      (node (ref "ADC0") (pin "5") (pinfunction "AIN0_5") (pintype "bidirectional"))
      (node (ref "BOARD_YZ") (pin "RATE_X") (pinfunction "RATE_RATE_X") (pintype "bidirectional"))
    )
    (net (code "54") (name "RATE_Y") (class "Default")
      (node (ref "ADC0") (pin "6") (pinfunction "AIN1_6") (pintype "bidirectional"))
      (node (ref "BOARD_XZ") (pin "RATE_Y") (pinfunction "RATE_RATE_Y") (pintype "bidirectional"))
    )
    (net (code "55") (name "RATE_Z") (class "Default")
      (node (ref "ADC0") (pin "7") (pinfunction "AIN2_7") (pintype "bidirectional"))
      (node (ref "C7") (pin "2") (pinfunction "2_2") (pintype "passive"))
      (node (ref "GYRO_Z") (pin "A2") (pinfunction "RATEOUT__A2") (pintype "bidirectional"))
      (node (ref "GYRO_Z") (pin "B1") (pinfunction "RATEOUT_B1") (pintype "bidirectional"))
    )
    (net (code "56") (name "SPI1_MISO") (class "Default")
      (node (ref "ADC0") (pin "1") (pinfunction "DOUT_1") (pintype "bidirectional"))
      (node (ref "MCU") (pin "53") (pinfunction "(CAP1.3/MISO1/MAT1.3)P0.18_53") (pintype "bidirectional"))
      (node (ref "U$9") (pin "P$2") (pinfunction "MISO_P$2") (pintype "bidirectional"))
    )
    (net (code "57") (name "SPI1_MOSI") (class "Default")
      (node (ref "ADC0") (pin "3") (pinfunction "DIN_3") (pintype "bidirectional"))
      (node (ref "MCU") (pin "54") (pinfunction "(MAT1.2/MOSI1/CAP1.2)P0.19_54") (pintype "bidirectional"))
      (node (ref "U$9") (pin "P$3") (pinfunction "MOSI_P$3") (pintype "bidirectional"))
    )
    (net (code "58") (name "SPI1_SCK") (class "Default")
      (node (ref "ADC0") (pin "2") (pinfunction "SCK_2") (pintype "bidirectional"))
      (node (ref "MCU") (pin "47") (pinfunction "(CAP1.2/SCK1/MAT1.2)P0.17_47") (pintype "bidirectional"))
      (node (ref "U$9") (pin "P$1") (pinfunction "SCLK_P$1") (pintype "bidirectional"))
    )
    (net (code "59") (name "SPI1_SS") (class "Default")
      (node (ref "MCU") (pin "55") (pinfunction "(MAT1.3/SSEL1/EINT3)P0.20_55") (pintype "bidirectional"))
      (node (ref "U$9") (pin "P$4") (pinfunction "SS_P$4") (pintype "bidirectional"))
    )
    (net (code "60") (name "ST1") (class "Default")
      (node (ref "GYRO_Z") (pin "F5") (pinfunction "ST1_F5") (pintype "bidirectional"))
      (node (ref "GYRO_Z") (pin "G5") (pinfunction "ST1__G5") (pintype "bidirectional"))
    )
    (net (code "61") (name "ST2") (class "Default")
      (node (ref "GYRO_Z") (pin "F4") (pinfunction "ST2_F4") (pintype "bidirectional"))
      (node (ref "GYRO_Z") (pin "G4") (pinfunction "ST2__G4") (pintype "bidirectional"))
    )
    (net (code "62") (name "TEMP") (class "Default")
      (node (ref "ADC0") (pin "8") (pinfunction "AIN3_8") (pintype "bidirectional"))
      (node (ref "GYRO_Z") (pin "F3") (pinfunction "TEMP_F3") (pintype "bidirectional"))
      (node (ref "GYRO_Z") (pin "G3") (pinfunction "TEMP__G3") (pintype "bidirectional"))
    )
    (net (code "63") (name "USB+") (class "Default")
      (node (ref "R9") (pin "1") (pinfunction "1_1") (pintype "passive"))
      (node (ref "SERIAL_1") (pin "5") (pinfunction "S_5") (pintype "passive"))
    )
    (net (code "64") (name "USB-") (class "Default")
      (node (ref "R10") (pin "1") (pinfunction "1_1") (pintype "passive"))
      (node (ref "SERIAL_1") (pin "6") (pinfunction "S_6") (pintype "passive"))
    )
    (net (code "65") (name "VBAT_LIPO") (class "Default")
      (node (ref "C18") (pin "+") (pinfunction "+_+") (pintype "passive"))
      (node (ref "IC1") (pin "1") (pinfunction "IN_1") (pintype "input"))
      (node (ref "IC1") (pin "3") (pinfunction "EN_3") (pintype "input"))
      (node (ref "IC2") (pin "3") (pinfunction "VIN_3") (pintype "input"))
      (node (ref "R24") (pin "2") (pinfunction "2_2") (pintype "passive"))
      (node (ref "X6") (pin "1") (pinfunction "S_1") (pintype "passive"))
    )
    (net (code "66") (name "VBAT_MEAS") (class "Default")
      (node (ref "C34") (pin "2") (pinfunction "2_2") (pintype "passive"))
      (node (ref "MCU") (pin "9") (pinfunction "(AD0.4/AOUT)P0.25_9") (pintype "bidirectional"))
      (node (ref "R24") (pin "1") (pinfunction "1_1") (pintype "passive"))
      (node (ref "R25") (pin "2") (pinfunction "2_2") (pintype "passive"))
    )
    (net (code "67") (name "unconnected-(MCU-(CTS1{slash}CAP1.1{slash}SCL1)P0.11-Pad37)") (class "Default")
      (node (ref "MCU") (pin "37") (pinfunction "(CTS1/CAP1.1/SCL1)P0.11_37") (pintype "bidirectional"))
    )
    (net (code "68") (name "unconnected-(MCU-P1.17(TRACEPKT1)-Pad12)") (class "Default")
      (node (ref "MCU") (pin "12") (pinfunction "P1.17(TRACEPKT1)_12") (pintype "bidirectional"))
    )
    (net (code "69") (name "unconnected-(MCU-P1.18(TRACEPKT2)-Pad8)") (class "Default")
      (node (ref "MCU") (pin "8") (pinfunction "P1.18(TRACEPKT2)_8") (pintype "bidirectional"))
    )
    (net (code "70") (name "unconnected-(MCU-P1.19(TRACEPKT3)-Pad4)") (class "Default")
      (node (ref "MCU") (pin "4") (pinfunction "P1.19(TRACEPKT3)_4") (pintype "bidirectional"))
    )
    (net (code "71") (name "unconnected-(MCU-P1.20(TRACESYNC)-Pad48)") (class "Default")
      (node (ref "MCU") (pin "48") (pinfunction "P1.20(TRACESYNC)_48") (pintype "bidirectional"))
    )
    (net (code "72") (name "unconnected-(MCU-P1.22(PIPESTAT1)-Pad40)") (class "Default")
      (node (ref "MCU") (pin "40") (pinfunction "P1.22(PIPESTAT1)_40") (pintype "bidirectional"))
    )
    (net (code "73") (name "unconnected-(MCU-P1.23(PIPESTAT2)-Pad36)") (class "Default")
      (node (ref "MCU") (pin "36") (pinfunction "P1.23(PIPESTAT2)_36") (pintype "bidirectional"))
    )
    (net (code "74") (name "unconnected-(MCU-P1.25(EXTIN0)-Pad28)") (class "Default")
      (node (ref "MCU") (pin "28") (pinfunction "P1.25(EXTIN0)_28") (pintype "bidirectional"))
    )
    (net (code "75") (name "unconnected-(MCU-P1.26(RTCK)-Pad24)") (class "Default")
      (node (ref "MCU") (pin "24") (pinfunction "P1.26(RTCK)_24") (pintype "bidirectional"))
    )
    (net (code "76") (name "unconnected-(MCU-P1.27(TDO)-Pad64)") (class "Default")
      (node (ref "MCU") (pin "64") (pinfunction "P1.27(TDO)_64") (pintype "bidirectional"))
    )
    (net (code "77") (name "unconnected-(MCU-P1.28(TDI)-Pad60)") (class "Default")
      (node (ref "MCU") (pin "60") (pinfunction "P1.28(TDI)_60") (pintype "bidirectional"))
    )
    (net (code "78") (name "unconnected-(MCU-P1.30(TMS)-Pad52)") (class "Default")
      (node (ref "MCU") (pin "52") (pinfunction "P1.30(TMS)_52") (pintype "bidirectional"))
    )
    (net (code "79") (name "unconnected-(MCU-P1.31({slash}TRST)-Pad20)") (class "Default")
      (node (ref "MCU") (pin "20") (pinfunction "P1.31(/TRST)_20") (pintype "bidirectional"))
    )
    (net (code "80") (name "unconnected-(MCU-RTXC1-Pad3)") (class "Default")
      (node (ref "MCU") (pin "3") (pinfunction "RTXC1_3") (pintype "input"))
    )
    (net (code "81") (name "unconnected-(MCU-RTXC2-Pad5)") (class "Default")
      (node (ref "MCU") (pin "5") (pinfunction "RTXC2_5") (pintype "output"))
    )
    (net (code "82") (name "unconnected-(U$9-NC1-PadP$8)") (class "Default")
      (node (ref "U$9") (pin "P$8") (pinfunction "NC1_P$8") (pintype "bidirectional"))
    )
    (net (code "83") (name "unconnected-(U$9-NC2-PadP$9)") (class "Default")
      (node (ref "U$9") (pin "P$9") (pinfunction "NC2_P$9") (pintype "bidirectional"))
    )
    (net (code "84") (name "unconnected-(U$9-NC3-PadP$10)") (class "Default")
      (node (ref "U$9") (pin "P$10") (pinfunction "NC3_P$10") (pintype "bidirectional"))
    )
    (net (code "85") (name "unconnected-(U$9-NC4-PadP$11)") (class "Default")
      (node (ref "U$9") (pin "P$11") (pinfunction "NC4_P$11") (pintype "bidirectional"))
    )
    (net (code "86") (name "unconnected-(U$9-NC5-PadP$13)") (class "Default")
      (node (ref "U$9") (pin "P$13") (pinfunction "NC5_P$13") (pintype "bidirectional"))
    )
  )
)
